# serduchotron_2.net
KiCad netlist of a schematic drawn in EAGLE
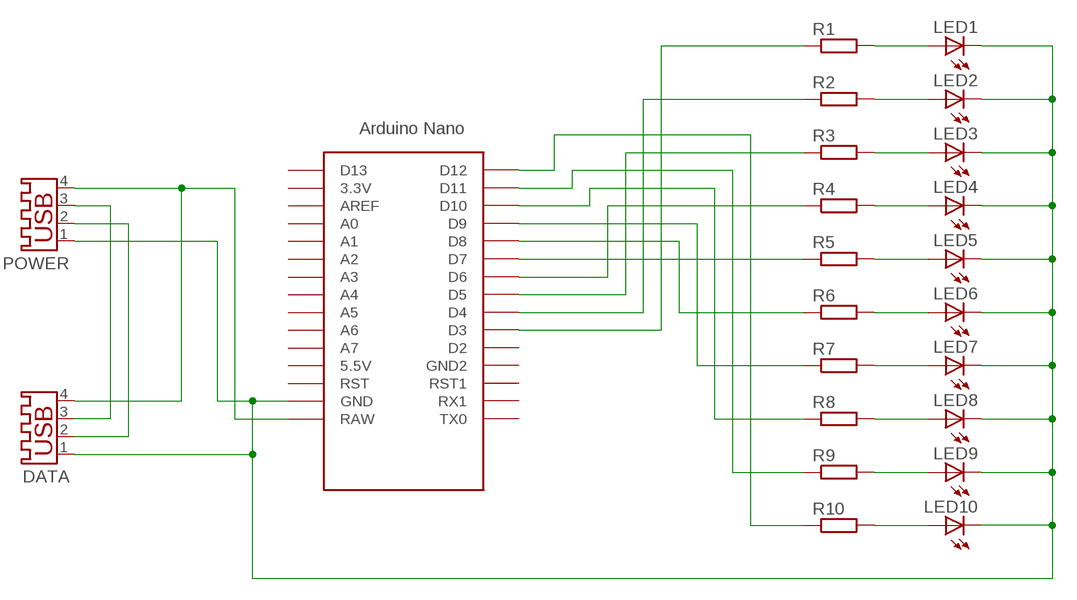
[diagram p0: schematic, sheet 1]

(export (version "E")
  (design (tool "Eeschema 10.0.6"))
  (components
    (comp (ref "DATA")
      (value "USB-A003")
      (footprint "eagle-import:USB-A003")
      (libsource (lib "eagle-import") (part "USB-A003"))
    )
    (comp (ref "LED1")
      (value "LEDCHIP-LED0805")
      (footprint "eagle-import:CHIP-LED0805")
      (libsource (lib "eagle-import") (part "LEDCHIP-LED0805"))
    )
    (comp (ref "LED2")
      (value "LEDCHIP-LED0805")
      (footprint "eagle-import:CHIP-LED0805")
      (libsource (lib "eagle-import") (part "LEDCHIP-LED0805"))
    )
    (comp (ref "LED3")
      (value "LEDCHIP-LED0805")
      (footprint "eagle-import:CHIP-LED0805")
      (libsource (lib "eagle-import") (part "LEDCHIP-LED0805"))
    )
    (comp (ref "LED4")
      (value "LEDCHIP-LED0805")
      (footprint "eagle-import:CHIP-LED0805")
      (libsource (lib "eagle-import") (part "LEDCHIP-LED0805"))
    )
    (comp (ref "LED5")
      (value "LEDCHIP-LED0805")
      (footprint "eagle-import:CHIP-LED0805")
      (libsource (lib "eagle-import") (part "LEDCHIP-LED0805"))
    )
    (comp (ref "LED6")
      (value "LEDCHIP-LED0805")
      (footprint "eagle-import:CHIP-LED0805")
      (libsource (lib "eagle-import") (part "LEDCHIP-LED0805"))
    )
    (comp (ref "LED7")
      (value "LEDCHIP-LED0805")
      (footprint "eagle-import:CHIP-LED0805")
      (libsource (lib "eagle-import") (part "LEDCHIP-LED0805"))
    )
    (comp (ref "LED8")
      (value "LEDCHIP-LED0805")
      (footprint "eagle-import:CHIP-LED0805")
      (libsource (lib "eagle-import") (part "LEDCHIP-LED0805"))
    )
    (comp (ref "LED9")
      (value "LEDCHIP-LED0805")
      (footprint "eagle-import:CHIP-LED0805")
      (libsource (lib "eagle-import") (part "LEDCHIP-LED0805"))
    )
    (comp (ref "LED10")
      (value "LEDCHIP-LED0805")
      (footprint "eagle-import:CHIP-LED0805")
      (libsource (lib "eagle-import") (part "LEDCHIP-LED0805"))
    )
    (comp (ref "POWER")
      (value "USB-A003")
      (footprint "eagle-import:USB-A003")
      (libsource (lib "eagle-import") (part "USB-A003"))
    )
    (comp (ref "R1")
      (value "R-EU_M0805")
      (footprint "eagle-import:M0805")
      (libsource (lib "eagle-import") (part "R-EU_M0805"))
    )
    (comp (ref "R2")
      (value "R-EU_M0805")
      (footprint "eagle-import:M0805")
      (libsource (lib "eagle-import") (part "R-EU_M0805"))
    )
    (comp (ref "R3")
      (value "R-EU_M0805")
      (footprint "eagle-import:M0805")
      (libsource (lib "eagle-import") (part "R-EU_M0805"))
    )
    (comp (ref "R4")
      (value "R-EU_M0805")
      (footprint "eagle-import:M0805")
      (libsource (lib "eagle-import") (part "R-EU_M0805"))
    )
    (comp (ref "R5")
      (value "R-EU_M0805")
      (footprint "eagle-import:M0805")
      (libsource (lib "eagle-import") (part "R-EU_M0805"))
    )
    (comp (ref "R6")
      (value "R-EU_M0805")
      (footprint "eagle-import:M0805")
      (libsource (lib "eagle-import") (part "R-EU_M0805"))
    )
    (comp (ref "R7")
      (value "R-EU_M0805")
      (footprint "eagle-import:M0805")
      (libsource (lib "eagle-import") (part "R-EU_M0805"))
    )
    (comp (ref "R8")
      (value "R-EU_M0805")
      (footprint "eagle-import:M0805")
      (libsource (lib "eagle-import") (part "R-EU_M0805"))
    )
    (comp (ref "R9")
      (value "R-EU_M0805")
      (footprint "eagle-import:M0805")
      (libsource (lib "eagle-import") (part "R-EU_M0805"))
    )
    (comp (ref "R10")
      (value "R-EU_M0805")
      (footprint "eagle-import:M0805")
      (libsource (lib "eagle-import") (part "R-EU_M0805"))
    )
    (comp (ref "U$1")
      (value "NANO")
      (footprint "eagle-import:NANO")
      (libsource (lib "eagle-import") (part "NANO"))
    )
  )
  (nets
    (net (code "1") (name "Net-(DATA-Pad1)") (class "Default")
      (node (ref "DATA") (pin "1") (pinfunction "1_1") (pintype "passive"))
      (node (ref "LED1") (pin "C") (pinfunction "C_C") (pintype "passive"))
      (node (ref "LED10") (pin "C") (pinfunction "C_C") (pintype "passive"))
      (node (ref "LED2") (pin "C") (pinfunction "C_C") (pintype "passive"))
      (node (ref "LED3") (pin "C") (pinfunction "C_C") (pintype "passive"))
      (node (ref "LED4") (pin "C") (pinfunction "C_C") (pintype "passive"))
      (node (ref "LED5") (pin "C") (pinfunction "C_C") (pintype "passive"))
      (node (ref "LED6") (pin "C") (pinfunction "C_C") (pintype "passive"))
      (node (ref "LED7") (pin "C") (pinfunction "C_C") (pintype "passive"))
      (node (ref "LED8") (pin "C") (pinfunction "C_C") (pintype "passive"))
      (node (ref "LED9") (pin "C") (pinfunction "C_C") (pintype "passive"))
      (node (ref "POWER") (pin "1") (pinfunction "1_1") (pintype "passive"))
      (node (ref "U$1") (pin "GND") (pinfunction "GND_GND") (pintype "bidirectional"))
    )
    (net (code "2") (name "Net-(DATA-Pad2)") (class "Default")
      (node (ref "DATA") (pin "2") (pinfunction "2_2") (pintype "passive"))
      (node (ref "POWER") (pin "2") (pinfunction "2_2") (pintype "passive"))
    )
    (net (code "3") (name "Net-(DATA-Pad3)") (class "Default")
      (node (ref "DATA") (pin "3") (pinfunction "3_3") (pintype "passive"))
      (node (ref "POWER") (pin "3") (pinfunction "3_3") (pintype "passive"))
    )
    (net (code "4") (name "Net-(DATA-Pad4)") (class "Default")
      (node (ref "DATA") (pin "4") (pinfunction "4_4") (pintype "passive"))
      (node (ref "POWER") (pin "4") (pinfunction "4_4") (pintype "passive"))
      (node (ref "U$1") (pin "RAW") (pinfunction "RAW_RAW") (pintype "bidirectional"))
    )
    (net (code "5") (name "Net-(LED1-PadA)") (class "Default")
      (node (ref "LED1") (pin "A") (pinfunction "A_A") (pintype "passive"))
      (node (ref "R1") (pin "2") (pinfunction "2_2") (pintype "passive"))
    )
    (net (code "6") (name "Net-(LED2-PadA)") (class "Default")
      (node (ref "LED2") (pin "A") (pinfunction "A_A") (pintype "passive"))
      (node (ref "R2") (pin "2") (pinfunction "2_2") (pintype "passive"))
    )
    (net (code "7") (name "Net-(LED3-PadA)") (class "Default")
      (node (ref "LED3") (pin "A") (pinfunction "A_A") (pintype "passive"))
      (node (ref "R3") (pin "2") (pinfunction "2_2") (pintype "passive"))
    )
    (net (code "8") (name "Net-(LED4-PadA)") (class "Default")
      (node (ref "LED4") (pin "A") (pinfunction "A_A") (pintype "passive"))
      (node (ref "R4") (pin "2") (pinfunction "2_2") (pintype "passive"))
    )
    (net (code "9") (name "Net-(LED5-PadA)") (class "Default")
      (node (ref "LED5") (pin "A") (pinfunction "A_A") (pintype "passive"))
      (node (ref "R5") (pin "2") (pinfunction "2_2") (pintype "passive"))
    )
    (net (code "10") (name "Net-(LED6-PadA)") (class "Default")
      (node (ref "LED6") (pin "A") (pinfunction "A_A") (pintype "passive"))
      (node (ref "R6") (pin "2") (pinfunction "2_2") (pintype "passive"))
    )
    (net (code "11") (name "Net-(LED7-PadA)") (class "Default")
      (node (ref "LED7") (pin "A") (pinfunction "A_A") (pintype "passive"))
      (node (ref "R7") (pin "2") (pinfunction "2_2") (pintype "passive"))
    )
    (net (code "12") (name "Net-(LED8-PadA)") (class "Default")
      (node (ref "LED8") (pin "A") (pinfunction "A_A") (pintype "passive"))
      (node (ref "R8") (pin "2") (pinfunction "2_2") (pintype "passive"))
    )
    (net (code "13") (name "Net-(LED9-PadA)") (class "Default")
      (node (ref "LED9") (pin "A") (pinfunction "A_A") (pintype "passive"))
      (node (ref "R9") (pin "2") (pinfunction "2_2") (pintype "passive"))
    )
    (net (code "14") (name "Net-(LED10-PadA)") (class "Default")
      (node (ref "LED10") (pin "A") (pinfunction "A_A") (pintype "passive"))
      (node (ref "R10") (pin "2") (pinfunction "2_2") (pintype "passive"))
    )
    (net (code "15") (name "Net-(R1-Pad1)") (class "Default")
      (node (ref "R1") (pin "1") (pinfunction "1_1") (pintype "passive"))
      (node (ref "U$1") (pin "D3") (pinfunction "D3_D3") (pintype "bidirectional"))
    )
    (net (code "16") (name "Net-(R2-Pad1)") (class "Default")
      (node (ref "R2") (pin "1") (pinfunction "1_1") (pintype "passive"))
      (node (ref "U$1") (pin "D4") (pinfunction "D4_D4") (pintype "bidirectional"))
    )
    (net (code "17") (name "Net-(R3-Pad1)") (class "Default")
      (node (ref "R3") (pin "1") (pinfunction "1_1") (pintype "passive"))
      (node (ref "U$1") (pin "D5") (pinfunction "D5_D5") (pintype "bidirectional"))
    )
    (net (code "18") (name "Net-(R4-Pad1)") (class "Default")
      (node (ref "R4") (pin "1") (pinfunction "1_1") (pintype "passive"))
      (node (ref "U$1") (pin "D6") (pinfunction "D6_D6") (pintype "bidirectional"))
    )
    (net (code "19") (name "Net-(R5-Pad1)") (class "Default")
      (node (ref "R5") (pin "1") (pinfunction "1_1") (pintype "passive"))
      (node (ref "U$1") (pin "D7") (pinfunction "D7_D7") (pintype "bidirectional"))
    )
    (net (code "20") (name "Net-(R6-Pad1)") (class "Default")
      (node (ref "R6") (pin "1") (pinfunction "1_1") (pintype "passive"))
      (node (ref "U$1") (pin "D8") (pinfunction "D8_D8") (pintype "bidirectional"))
    )
    (net (code "21") (name "Net-(R7-Pad1)") (class "Default")
      (node (ref "R7") (pin "1") (pinfunction "1_1") (pintype "passive"))
      (node (ref "U$1") (pin "D9") (pinfunction "D9_D9") (pintype "bidirectional"))
    )
    (net (code "22") (name "Net-(R8-Pad1)") (class "Default")
      (node (ref "R8") (pin "1") (pinfunction "1_1") (pintype "passive"))
      (node (ref "U$1") (pin "D10") (pinfunction "D10_D10") (pintype "bidirectional"))
    )
    (net (code "23") (name "Net-(R9-Pad1)") (class "Default")
      (node (ref "R9") (pin "1") (pinfunction "1_1") (pintype "passive"))
      (node (ref "U$1") (pin "D11") (pinfunction "D11_D11") (pintype "bidirectional"))
    )
    (net (code "24") (name "Net-(R10-Pad1)") (class "Default")
      (node (ref "R10") (pin "1") (pinfunction "1_1") (pintype "passive"))
      (node (ref "U$1") (pin "D12") (pinfunction "D12_D12") (pintype "bidirectional"))
    )
    (net (code "25") (name "unconnected-(U$1-5.5V-Pad5V)") (class "Default")
      (node (ref "U$1") (pin "5V") (pinfunction "5.5V_5V") (pintype "bidirectional"))
    )
    (net (code "26") (name "unconnected-(U$1-GND2-PadGND1)") (class "Default")
      (node (ref "U$1") (pin "GND1") (pinfunction "GND2_GND1") (pintype "bidirectional"))
    )
    (net (code "27") (name "unconnected-(U$1-Pad3.3V)") (class "Default")
      (node (ref "U$1") (pin "3.3V") (pinfunction "3.3V_3.3V") (pintype "bidirectional"))
    )
    (net (code "28") (name "unconnected-(U$1-PadA0)") (class "Default")
      (node (ref "U$1") (pin "A0") (pinfunction "A0_A0") (pintype "bidirectional"))
    )
    (net (code "29") (name "unconnected-(U$1-PadA1)") (class "Default")
      (node (ref "U$1") (pin "A1") (pinfunction "A1_A1") (pintype "bidirectional"))
    )
    (net (code "30") (name "unconnected-(U$1-PadA2)") (class "Default")
      (node (ref "U$1") (pin "A2") (pinfunction "A2_A2") (pintype "bidirectional"))
    )
    (net (code "31") (name "unconnected-(U$1-PadA3)") (class "Default")
      (node (ref "U$1") (pin "A3") (pinfunction "A3_A3") (pintype "bidirectional"))
    )
    (net (code "32") (name "unconnected-(U$1-PadA4)") (class "Default")
      (node (ref "U$1") (pin "A4") (pinfunction "A4_A4") (pintype "bidirectional"))
    )
    (net (code "33") (name "unconnected-(U$1-PadA5)") (class "Default")
      (node (ref "U$1") (pin "A5") (pinfunction "A5_A5") (pintype "bidirectional"))
    )
    (net (code "34") (name "unconnected-(U$1-PadA6)") (class "Default")
      (node (ref "U$1") (pin "A6") (pinfunction "A6_A6") (pintype "bidirectional"))
    )
    (net (code "35") (name "unconnected-(U$1-PadA7)") (class "Default")
      (node (ref "U$1") (pin "A7") (pinfunction "A7_A7") (pintype "bidirectional"))
    )
    (net (code "36") (name "unconnected-(U$1-PadAREF)") (class "Default")
      (node (ref "U$1") (pin "AREF") (pinfunction "AREF_AREF") (pintype "bidirectional"))
    )
    (net (code "37") (name "unconnected-(U$1-PadD2)") (class "Default")
      (node (ref "U$1") (pin "D2") (pinfunction "D2_D2") (pintype "bidirectional"))
    )
    (net (code "38") (name "unconnected-(U$1-PadD13)") (class "Default")
      (node (ref "U$1") (pin "D13") (pinfunction "D13_D13") (pintype "bidirectional"))
    )
    (net (code "39") (name "unconnected-(U$1-PadICSP1)") (class "Default")
      (node (ref "U$1") (pin "ICSP1") (pinfunction "ICSP1_ICSP1") (pintype "bidirectional"))
    )
    (net (code "40") (name "unconnected-(U$1-PadICSP2)") (class "Default")
      (node (ref "U$1") (pin "ICSP2") (pinfunction "ICSP2_ICSP2") (pintype "bidirectional"))
    )
    (net (code "41") (name "unconnected-(U$1-PadICSP3)") (class "Default")
      (node (ref "U$1") (pin "ICSP3") (pinfunction "ICSP3_ICSP3") (pintype "bidirectional"))
    )
    (net (code "42") (name "unconnected-(U$1-PadICSP4)") (class "Default")
      (node (ref "U$1") (pin "ICSP4") (pinfunction "ICSP4_ICSP4") (pintype "bidirectional"))
    )
    (net (code "43") (name "unconnected-(U$1-PadICSP5)") (class "Default")
      (node (ref "U$1") (pin "ICSP5") (pinfunction "ICSP5_ICSP5") (pintype "bidirectional"))
    )
    (net (code "44") (name "unconnected-(U$1-PadICSP6)") (class "Default")
      (node (ref "U$1") (pin "ICSP6") (pinfunction "ICSP6_ICSP6") (pintype "bidirectional"))
    )
    (net (code "45") (name "unconnected-(U$1-PadRST)") (class "Default")
      (node (ref "U$1") (pin "RST") (pinfunction "RST_RST") (pintype "bidirectional"))
    )
    (net (code "46") (name "unconnected-(U$1-PadRST1)") (class "Default")
      (node (ref "U$1") (pin "RST1") (pinfunction "RST1_RST1") (pintype "bidirectional"))
    )
    (net (code "47") (name "unconnected-(U$1-PadRX1)") (class "Default")
      (node (ref "U$1") (pin "RX1") (pinfunction "RX1_RX1") (pintype "bidirectional"))
    )
    (net (code "48") (name "unconnected-(U$1-PadTX0)") (class "Default")
      (node (ref "U$1") (pin "TX0") (pinfunction "TX0_TX0") (pintype "bidirectional"))
    )
  )
)
